# BlackIceMx.net
KiCad netlist of a schematic drawn in EAGLE
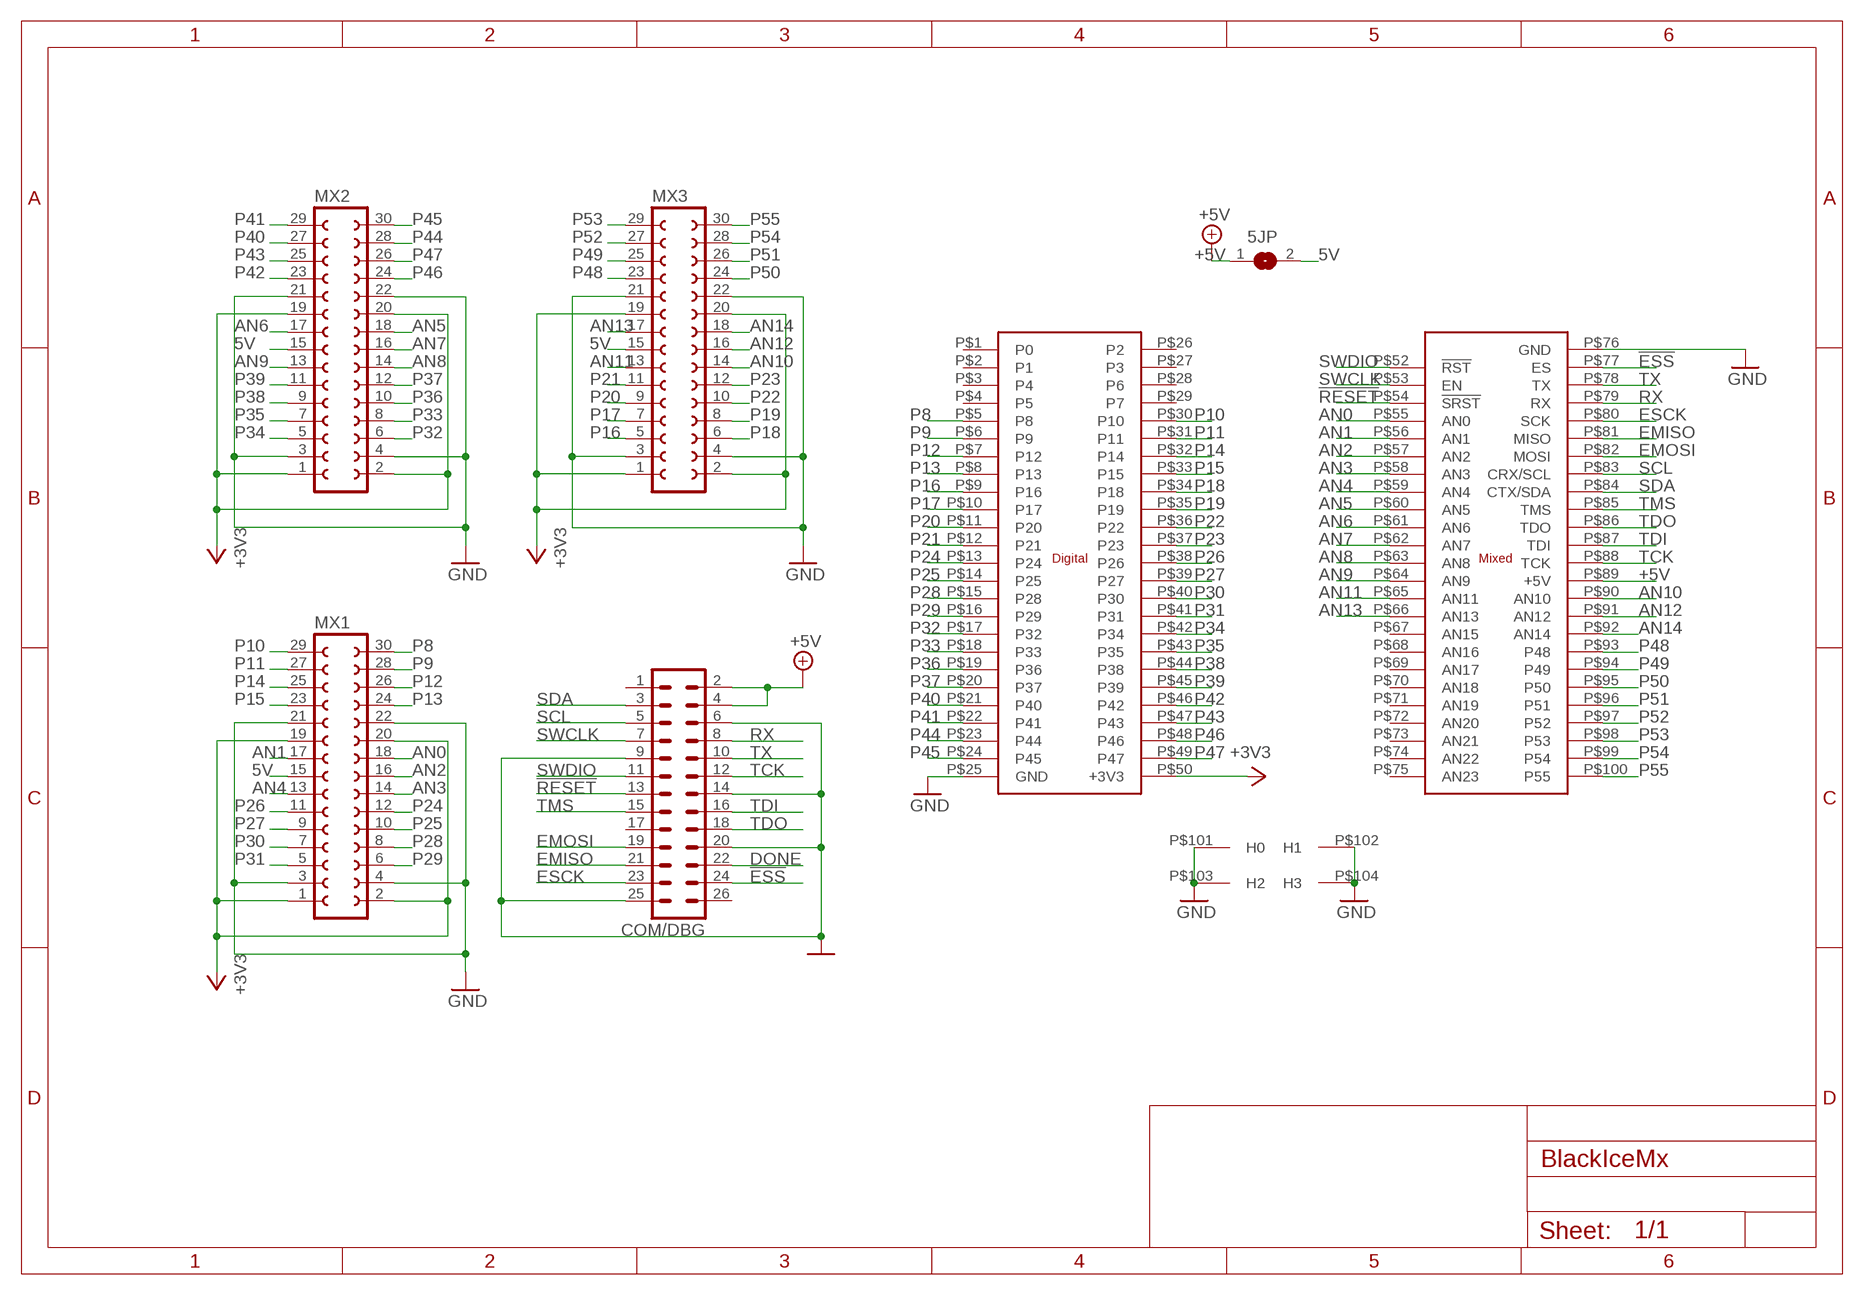
[diagram p0: schematic, sheet 1]

(export (version "E")
  (design (tool "Eeschema 10.0.6"))
  (components
    (comp (ref "5JP") (value "SJ") (footprint "eagle-import:SJ") (libsource (lib "eagle-import") (part "SJ")))
    (comp (ref "COM/DBG")
      (value "MA13-2")
      (footprint "eagle-import:MA13-2")
      (libsource (lib "eagle-import") (part "MA13-2"))
    )
    (comp (ref "MX1")
      (value "FE15-2")
      (footprint "eagle-import:FE15-2")
      (libsource (lib "eagle-import") (part "FE15-2"))
    )
    (comp (ref "MX2")
      (value "FE15-2")
      (footprint "eagle-import:FE15-2")
      (libsource (lib "eagle-import") (part "FE15-2"))
    )
    (comp (ref "MX3")
      (value "FE15-2")
      (footprint "eagle-import:FE15-2")
      (libsource (lib "eagle-import") (part "FE15-2"))
    )
    (comp (ref "U$1")
      (value "BE-CARRIERSMD")
      (footprint "eagle-import:BE-CARRIER-SMD")
      (libsource (lib "eagle-import") (part "BE-CARRIERSMD"))
    )
  )
  (nets
    (net (code "1") (name "+3V3") (class "Default")
      (node (ref "MX1") (pin "1") (pinfunction "1_1") (pintype "passive"))
      (node (ref "MX1") (pin "19") (pinfunction "19_19") (pintype "passive"))
      (node (ref "MX1") (pin "2") (pinfunction "2_2") (pintype "passive"))
      (node (ref "MX1") (pin "20") (pinfunction "20_20") (pintype "passive"))
      (node (ref "MX2") (pin "1") (pinfunction "1_1") (pintype "passive"))
      (node (ref "MX2") (pin "19") (pinfunction "19_19") (pintype "passive"))
      (node (ref "MX2") (pin "2") (pinfunction "2_2") (pintype "passive"))
      (node (ref "MX2") (pin "20") (pinfunction "20_20") (pintype "passive"))
      (node (ref "MX3") (pin "1") (pinfunction "1_1") (pintype "passive"))
      (node (ref "MX3") (pin "19") (pinfunction "19_19") (pintype "passive"))
      (node (ref "MX3") (pin "2") (pinfunction "2_2") (pintype "passive"))
      (node (ref "MX3") (pin "20") (pinfunction "20_20") (pintype "passive"))
      (node (ref "U$1") (pin "P$50") (pinfunction "+3V3_P$50") (pintype "power_in"))
    )
    (net (code "2") (name "+5V") (class "Default")
      (node (ref "5JP") (pin "1") (pinfunction "1_1") (pintype "passive"))
      (node (ref "COM/DBG") (pin "2") (pinfunction "2_2") (pintype "passive"))
      (node (ref "COM/DBG") (pin "4") (pinfunction "4_4") (pintype "passive"))
      (node (ref "U$1") (pin "P$89") (pinfunction "+5V_P$89") (pintype "power_in"))
    )
    (net (code "3") (name "/5V") (class "Default")
      (node (ref "5JP") (pin "2") (pinfunction "2_2") (pintype "passive"))
      (node (ref "MX1") (pin "15") (pinfunction "15_15") (pintype "passive"))
      (node (ref "MX2") (pin "15") (pinfunction "15_15") (pintype "passive"))
      (node (ref "MX3") (pin "15") (pinfunction "15_15") (pintype "passive"))
    )
    (net (code "4") (name "/AN0") (class "Default")
      (node (ref "MX1") (pin "18") (pinfunction "18_18") (pintype "passive"))
      (node (ref "U$1") (pin "P$55") (pinfunction "AN0_P$55") (pintype "bidirectional"))
    )
    (net (code "5") (name "/AN1") (class "Default")
      (node (ref "MX1") (pin "17") (pinfunction "17_17") (pintype "passive"))
      (node (ref "U$1") (pin "P$56") (pinfunction "AN1_P$56") (pintype "bidirectional"))
    )
    (net (code "6") (name "/AN2") (class "Default")
      (node (ref "MX1") (pin "16") (pinfunction "16_16") (pintype "passive"))
      (node (ref "U$1") (pin "P$57") (pinfunction "AN2_P$57") (pintype "bidirectional"))
    )
    (net (code "7") (name "/AN3") (class "Default")
      (node (ref "MX1") (pin "14") (pinfunction "14_14") (pintype "passive"))
      (node (ref "U$1") (pin "P$58") (pinfunction "AN3_P$58") (pintype "bidirectional"))
    )
    (net (code "8") (name "/AN4") (class "Default")
      (node (ref "MX1") (pin "13") (pinfunction "13_13") (pintype "passive"))
      (node (ref "U$1") (pin "P$59") (pinfunction "AN4_P$59") (pintype "bidirectional"))
    )
    (net (code "9") (name "/AN5") (class "Default")
      (node (ref "MX2") (pin "18") (pinfunction "18_18") (pintype "passive"))
      (node (ref "U$1") (pin "P$60") (pinfunction "AN5_P$60") (pintype "bidirectional"))
    )
    (net (code "10") (name "/AN6") (class "Default")
      (node (ref "MX2") (pin "17") (pinfunction "17_17") (pintype "passive"))
      (node (ref "U$1") (pin "P$61") (pinfunction "AN6_P$61") (pintype "bidirectional"))
    )
    (net (code "11") (name "/AN7") (class "Default")
      (node (ref "MX2") (pin "16") (pinfunction "16_16") (pintype "passive"))
      (node (ref "U$1") (pin "P$62") (pinfunction "AN7_P$62") (pintype "bidirectional"))
    )
    (net (code "12") (name "/AN8") (class "Default")
      (node (ref "MX2") (pin "14") (pinfunction "14_14") (pintype "passive"))
      (node (ref "U$1") (pin "P$63") (pinfunction "AN8_P$63") (pintype "bidirectional"))
    )
    (net (code "13") (name "/AN9") (class "Default")
      (node (ref "MX2") (pin "13") (pinfunction "13_13") (pintype "passive"))
      (node (ref "U$1") (pin "P$64") (pinfunction "AN9_P$64") (pintype "bidirectional"))
    )
    (net (code "14") (name "/AN10") (class "Default")
      (node (ref "MX3") (pin "14") (pinfunction "14_14") (pintype "passive"))
      (node (ref "U$1") (pin "P$90") (pinfunction "AN10_P$90") (pintype "bidirectional"))
    )
    (net (code "15") (name "/AN11") (class "Default")
      (node (ref "MX3") (pin "13") (pinfunction "13_13") (pintype "passive"))
      (node (ref "U$1") (pin "P$65") (pinfunction "AN11_P$65") (pintype "bidirectional"))
    )
    (net (code "16") (name "/AN12") (class "Default")
      (node (ref "MX3") (pin "16") (pinfunction "16_16") (pintype "passive"))
      (node (ref "U$1") (pin "P$91") (pinfunction "AN12_P$91") (pintype "bidirectional"))
    )
    (net (code "17") (name "/AN13") (class "Default")
      (node (ref "MX3") (pin "17") (pinfunction "17_17") (pintype "passive"))
      (node (ref "U$1") (pin "P$66") (pinfunction "AN13_P$66") (pintype "bidirectional"))
    )
    (net (code "18") (name "/AN14") (class "Default")
      (node (ref "MX3") (pin "18") (pinfunction "18_18") (pintype "passive"))
      (node (ref "U$1") (pin "P$92") (pinfunction "AN14_P$92") (pintype "bidirectional"))
    )
    (net (code "19") (name "/DONE") (class "Default")
      (node (ref "COM/DBG") (pin "22") (pinfunction "22_22") (pintype "passive"))
    )
    (net (code "20") (name "/EMISO") (class "Default")
      (node (ref "COM/DBG") (pin "21") (pinfunction "21_21") (pintype "passive"))
      (node (ref "U$1") (pin "P$81") (pinfunction "MISO_P$81") (pintype "bidirectional"))
    )
    (net (code "21") (name "/EMOSI") (class "Default")
      (node (ref "COM/DBG") (pin "19") (pinfunction "19_19") (pintype "passive"))
      (node (ref "U$1") (pin "P$82") (pinfunction "MOSI_P$82") (pintype "bidirectional"))
    )
    (net (code "22") (name "/ESCK") (class "Default")
      (node (ref "COM/DBG") (pin "23") (pinfunction "23_23") (pintype "passive"))
      (node (ref "U$1") (pin "P$80") (pinfunction "SCK_P$80") (pintype "bidirectional"))
    )
    (net (code "23") (name "/P8") (class "Default")
      (node (ref "MX1") (pin "30") (pinfunction "30_30") (pintype "passive"))
      (node (ref "U$1") (pin "P$5") (pinfunction "P8_P$5") (pintype "bidirectional"))
    )
    (net (code "24") (name "/P9") (class "Default")
      (node (ref "MX1") (pin "28") (pinfunction "28_28") (pintype "passive"))
      (node (ref "U$1") (pin "P$6") (pinfunction "P9_P$6") (pintype "bidirectional"))
    )
    (net (code "25") (name "/P10") (class "Default")
      (node (ref "MX1") (pin "29") (pinfunction "29_29") (pintype "passive"))
      (node (ref "U$1") (pin "P$30") (pinfunction "P10_P$30") (pintype "bidirectional"))
    )
    (net (code "26") (name "/P11") (class "Default")
      (node (ref "MX1") (pin "27") (pinfunction "27_27") (pintype "passive"))
      (node (ref "U$1") (pin "P$31") (pinfunction "P11_P$31") (pintype "bidirectional"))
    )
    (net (code "27") (name "/P12") (class "Default")
      (node (ref "MX1") (pin "26") (pinfunction "26_26") (pintype "passive"))
      (node (ref "U$1") (pin "P$7") (pinfunction "P12_P$7") (pintype "bidirectional"))
    )
    (net (code "28") (name "/P13") (class "Default")
      (node (ref "MX1") (pin "24") (pinfunction "24_24") (pintype "passive"))
      (node (ref "U$1") (pin "P$8") (pinfunction "P13_P$8") (pintype "bidirectional"))
    )
    (net (code "29") (name "/P14") (class "Default")
      (node (ref "MX1") (pin "25") (pinfunction "25_25") (pintype "passive"))
      (node (ref "U$1") (pin "P$32") (pinfunction "P14_P$32") (pintype "bidirectional"))
    )
    (net (code "30") (name "/P15") (class "Default")
      (node (ref "MX1") (pin "23") (pinfunction "23_23") (pintype "passive"))
      (node (ref "U$1") (pin "P$33") (pinfunction "P15_P$33") (pintype "bidirectional"))
    )
    (net (code "31") (name "/P16") (class "Default")
      (node (ref "MX3") (pin "5") (pinfunction "5_5") (pintype "passive"))
      (node (ref "U$1") (pin "P$9") (pinfunction "P16_P$9") (pintype "bidirectional"))
    )
    (net (code "32") (name "/P17") (class "Default")
      (node (ref "MX3") (pin "7") (pinfunction "7_7") (pintype "passive"))
      (node (ref "U$1") (pin "P$10") (pinfunction "P17_P$10") (pintype "bidirectional"))
    )
    (net (code "33") (name "/P18") (class "Default")
      (node (ref "MX3") (pin "6") (pinfunction "6_6") (pintype "passive"))
      (node (ref "U$1") (pin "P$34") (pinfunction "P18_P$34") (pintype "bidirectional"))
    )
    (net (code "34") (name "/P19") (class "Default")
      (node (ref "MX3") (pin "8") (pinfunction "8_8") (pintype "passive"))
      (node (ref "U$1") (pin "P$35") (pinfunction "P19_P$35") (pintype "bidirectional"))
    )
    (net (code "35") (name "/P20") (class "Default")
      (node (ref "MX3") (pin "9") (pinfunction "9_9") (pintype "passive"))
      (node (ref "U$1") (pin "P$11") (pinfunction "P20_P$11") (pintype "bidirectional"))
    )
    (net (code "36") (name "/P21") (class "Default")
      (node (ref "MX3") (pin "11") (pinfunction "11_11") (pintype "passive"))
      (node (ref "U$1") (pin "P$12") (pinfunction "P21_P$12") (pintype "bidirectional"))
    )
    (net (code "37") (name "/P22") (class "Default")
      (node (ref "MX3") (pin "10") (pinfunction "10_10") (pintype "passive"))
      (node (ref "U$1") (pin "P$36") (pinfunction "P22_P$36") (pintype "bidirectional"))
    )
    (net (code "38") (name "/P23") (class "Default")
      (node (ref "MX3") (pin "12") (pinfunction "12_12") (pintype "passive"))
      (node (ref "U$1") (pin "P$37") (pinfunction "P23_P$37") (pintype "bidirectional"))
    )
    (net (code "39") (name "/P24") (class "Default")
      (node (ref "MX1") (pin "12") (pinfunction "12_12") (pintype "passive"))
      (node (ref "U$1") (pin "P$13") (pinfunction "P24_P$13") (pintype "bidirectional"))
    )
    (net (code "40") (name "/P25") (class "Default")
      (node (ref "MX1") (pin "10") (pinfunction "10_10") (pintype "passive"))
      (node (ref "U$1") (pin "P$14") (pinfunction "P25_P$14") (pintype "bidirectional"))
    )
    (net (code "41") (name "/P26") (class "Default")
      (node (ref "MX1") (pin "11") (pinfunction "11_11") (pintype "passive"))
      (node (ref "U$1") (pin "P$38") (pinfunction "P26_P$38") (pintype "bidirectional"))
    )
    (net (code "42") (name "/P27") (class "Default")
      (node (ref "MX1") (pin "9") (pinfunction "9_9") (pintype "passive"))
      (node (ref "U$1") (pin "P$39") (pinfunction "P27_P$39") (pintype "bidirectional"))
    )
    (net (code "43") (name "/P28") (class "Default")
      (node (ref "MX1") (pin "8") (pinfunction "8_8") (pintype "passive"))
      (node (ref "U$1") (pin "P$15") (pinfunction "P28_P$15") (pintype "bidirectional"))
    )
    (net (code "44") (name "/P29") (class "Default")
      (node (ref "MX1") (pin "6") (pinfunction "6_6") (pintype "passive"))
      (node (ref "U$1") (pin "P$16") (pinfunction "P29_P$16") (pintype "bidirectional"))
    )
    (net (code "45") (name "/P30") (class "Default")
      (node (ref "MX1") (pin "7") (pinfunction "7_7") (pintype "passive"))
      (node (ref "U$1") (pin "P$40") (pinfunction "P30_P$40") (pintype "bidirectional"))
    )
    (net (code "46") (name "/P31") (class "Default")
      (node (ref "MX1") (pin "5") (pinfunction "5_5") (pintype "passive"))
      (node (ref "U$1") (pin "P$41") (pinfunction "P31_P$41") (pintype "bidirectional"))
    )
    (net (code "47") (name "/P32") (class "Default")
      (node (ref "MX2") (pin "6") (pinfunction "6_6") (pintype "passive"))
      (node (ref "U$1") (pin "P$17") (pinfunction "P32_P$17") (pintype "bidirectional"))
    )
    (net (code "48") (name "/P33") (class "Default")
      (node (ref "MX2") (pin "8") (pinfunction "8_8") (pintype "passive"))
      (node (ref "U$1") (pin "P$18") (pinfunction "P33_P$18") (pintype "bidirectional"))
    )
    (net (code "49") (name "/P34") (class "Default")
      (node (ref "MX2") (pin "5") (pinfunction "5_5") (pintype "passive"))
      (node (ref "U$1") (pin "P$42") (pinfunction "P34_P$42") (pintype "bidirectional"))
    )
    (net (code "50") (name "/P35") (class "Default")
      (node (ref "MX2") (pin "7") (pinfunction "7_7") (pintype "passive"))
      (node (ref "U$1") (pin "P$43") (pinfunction "P35_P$43") (pintype "bidirectional"))
    )
    (net (code "51") (name "/P36") (class "Default")
      (node (ref "MX2") (pin "10") (pinfunction "10_10") (pintype "passive"))
      (node (ref "U$1") (pin "P$19") (pinfunction "P36_P$19") (pintype "bidirectional"))
    )
    (net (code "52") (name "/P37") (class "Default")
      (node (ref "MX2") (pin "12") (pinfunction "12_12") (pintype "passive"))
      (node (ref "U$1") (pin "P$20") (pinfunction "P37_P$20") (pintype "bidirectional"))
    )
    (net (code "53") (name "/P38") (class "Default")
      (node (ref "MX2") (pin "9") (pinfunction "9_9") (pintype "passive"))
      (node (ref "U$1") (pin "P$44") (pinfunction "P38_P$44") (pintype "bidirectional"))
    )
    (net (code "54") (name "/P39") (class "Default")
      (node (ref "MX2") (pin "11") (pinfunction "11_11") (pintype "passive"))
      (node (ref "U$1") (pin "P$45") (pinfunction "P39_P$45") (pintype "bidirectional"))
    )
    (net (code "55") (name "/P40") (class "Default")
      (node (ref "MX2") (pin "27") (pinfunction "27_27") (pintype "passive"))
      (node (ref "U$1") (pin "P$21") (pinfunction "P40_P$21") (pintype "bidirectional"))
    )
    (net (code "56") (name "/P41") (class "Default")
      (node (ref "MX2") (pin "29") (pinfunction "29_29") (pintype "passive"))
      (node (ref "U$1") (pin "P$22") (pinfunction "P41_P$22") (pintype "bidirectional"))
    )
    (net (code "57") (name "/P42") (class "Default")
      (node (ref "MX2") (pin "23") (pinfunction "23_23") (pintype "passive"))
      (node (ref "U$1") (pin "P$46") (pinfunction "P42_P$46") (pintype "bidirectional"))
    )
    (net (code "58") (name "/P43") (class "Default")
      (node (ref "MX2") (pin "25") (pinfunction "25_25") (pintype "passive"))
      (node (ref "U$1") (pin "P$47") (pinfunction "P43_P$47") (pintype "bidirectional"))
    )
    (net (code "59") (name "/P44") (class "Default")
      (node (ref "MX2") (pin "28") (pinfunction "28_28") (pintype "passive"))
      (node (ref "U$1") (pin "P$23") (pinfunction "P44_P$23") (pintype "bidirectional"))
    )
    (net (code "60") (name "/P45") (class "Default")
      (node (ref "MX2") (pin "30") (pinfunction "30_30") (pintype "passive"))
      (node (ref "U$1") (pin "P$24") (pinfunction "P45_P$24") (pintype "bidirectional"))
    )
    (net (code "61") (name "/P46") (class "Default")
      (node (ref "MX2") (pin "24") (pinfunction "24_24") (pintype "passive"))
      (node (ref "U$1") (pin "P$48") (pinfunction "P46_P$48") (pintype "bidirectional"))
    )
    (net (code "62") (name "/P47") (class "Default")
      (node (ref "MX2") (pin "26") (pinfunction "26_26") (pintype "passive"))
      (node (ref "U$1") (pin "P$49") (pinfunction "P47_P$49") (pintype "bidirectional"))
    )
    (net (code "63") (name "/P48") (class "Default")
      (node (ref "MX3") (pin "23") (pinfunction "23_23") (pintype "passive"))
      (node (ref "U$1") (pin "P$93") (pinfunction "P48_P$93") (pintype "bidirectional"))
    )
    (net (code "64") (name "/P49") (class "Default")
      (node (ref "MX3") (pin "25") (pinfunction "25_25") (pintype "passive"))
      (node (ref "U$1") (pin "P$94") (pinfunction "P49_P$94") (pintype "bidirectional"))
    )
    (net (code "65") (name "/P50") (class "Default")
      (node (ref "MX3") (pin "24") (pinfunction "24_24") (pintype "passive"))
      (node (ref "U$1") (pin "P$95") (pinfunction "P50_P$95") (pintype "bidirectional"))
    )
    (net (code "66") (name "/P51") (class "Default")
      (node (ref "MX3") (pin "26") (pinfunction "26_26") (pintype "passive"))
      (node (ref "U$1") (pin "P$96") (pinfunction "P51_P$96") (pintype "bidirectional"))
    )
    (net (code "67") (name "/P52") (class "Default")
      (node (ref "MX3") (pin "27") (pinfunction "27_27") (pintype "passive"))
      (node (ref "U$1") (pin "P$97") (pinfunction "P52_P$97") (pintype "bidirectional"))
    )
    (net (code "68") (name "/P53") (class "Default")
      (node (ref "MX3") (pin "29") (pinfunction "29_29") (pintype "passive"))
      (node (ref "U$1") (pin "P$98") (pinfunction "P53_P$98") (pintype "bidirectional"))
    )
    (net (code "69") (name "/P54") (class "Default")
      (node (ref "MX3") (pin "28") (pinfunction "28_28") (pintype "passive"))
      (node (ref "U$1") (pin "P$99") (pinfunction "P54_P$99") (pintype "bidirectional"))
    )
    (net (code "70") (name "/P55") (class "Default")
      (node (ref "MX3") (pin "30") (pinfunction "30_30") (pintype "passive"))
      (node (ref "U$1") (pin "P$100") (pinfunction "P55_P$100") (pintype "bidirectional"))
    )
    (net (code "71") (name "/RX") (class "Default")
      (node (ref "COM/DBG") (pin "8") (pinfunction "8_8") (pintype "passive"))
      (node (ref "U$1") (pin "P$79") (pinfunction "RX_P$79") (pintype "bidirectional"))
    )
    (net (code "72") (name "/SCL") (class "Default")
      (node (ref "COM/DBG") (pin "5") (pinfunction "5_5") (pintype "passive"))
      (node (ref "U$1") (pin "P$83") (pinfunction "CRX/SCL_P$83") (pintype "bidirectional"))
    )
    (net (code "73") (name "/SDA") (class "Default")
      (node (ref "COM/DBG") (pin "3") (pinfunction "3_3") (pintype "passive"))
      (node (ref "U$1") (pin "P$84") (pinfunction "CTX/SDA_P$84") (pintype "bidirectional"))
    )
    (net (code "74") (name "/SWCLK") (class "Default")
      (node (ref "COM/DBG") (pin "7") (pinfunction "7_7") (pintype "passive"))
      (node (ref "U$1") (pin "P$53") (pinfunction "EN_P$53") (pintype "bidirectional"))
    )
    (net (code "75") (name "/SWDIO") (class "Default")
      (node (ref "COM/DBG") (pin "11") (pinfunction "11_11") (pintype "passive"))
      (node (ref "U$1") (pin "P$52") (pinfunction "~{RST}_P$52") (pintype "bidirectional"))
    )
    (net (code "76") (name "/TCK") (class "Default")
      (node (ref "COM/DBG") (pin "12") (pinfunction "12_12") (pintype "passive"))
      (node (ref "U$1") (pin "P$88") (pinfunction "TCK_P$88") (pintype "bidirectional"))
    )
    (net (code "77") (name "/TDI") (class "Default")
      (node (ref "COM/DBG") (pin "16") (pinfunction "16_16") (pintype "passive"))
      (node (ref "U$1") (pin "P$87") (pinfunction "TDI_P$87") (pintype "power_in"))
    )
    (net (code "78") (name "/TDO") (class "Default")
      (node (ref "COM/DBG") (pin "18") (pinfunction "18_18") (pintype "passive"))
      (node (ref "U$1") (pin "P$86") (pinfunction "TDO_P$86") (pintype "bidirectional"))
    )
    (net (code "79") (name "/TMS") (class "Default")
      (node (ref "COM/DBG") (pin "15") (pinfunction "15_15") (pintype "passive"))
      (node (ref "U$1") (pin "P$85") (pinfunction "TMS_P$85") (pintype "bidirectional"))
    )
    (net (code "80") (name "/TX") (class "Default")
      (node (ref "COM/DBG") (pin "10") (pinfunction "10_10") (pintype "passive"))
      (node (ref "U$1") (pin "P$78") (pinfunction "TX_P$78") (pintype "bidirectional"))
    )
    (net (code "81") (name "/~{ESS}") (class "Default")
      (node (ref "COM/DBG") (pin "24") (pinfunction "24_24") (pintype "passive"))
      (node (ref "U$1") (pin "P$77") (pinfunction "ES_P$77") (pintype "bidirectional"))
    )
    (net (code "82") (name "/~{RESET}") (class "Default")
      (node (ref "COM/DBG") (pin "13") (pinfunction "13_13") (pintype "passive"))
      (node (ref "U$1") (pin "P$54") (pinfunction "~{SRST}_P$54") (pintype "bidirectional"))
    )
    (net (code "83") (name "GND") (class "Default")
      (node (ref "COM/DBG") (pin "14") (pinfunction "14_14") (pintype "passive"))
      (node (ref "COM/DBG") (pin "20") (pinfunction "20_20") (pintype "passive"))
      (node (ref "COM/DBG") (pin "25") (pinfunction "25_25") (pintype "passive"))
      (node (ref "COM/DBG") (pin "6") (pinfunction "6_6") (pintype "passive"))
      (node (ref "COM/DBG") (pin "9") (pinfunction "9_9") (pintype "passive"))
      (node (ref "MX1") (pin "21") (pinfunction "21_21") (pintype "passive"))
      (node (ref "MX1") (pin "22") (pinfunction "22_22") (pintype "passive"))
      (node (ref "MX1") (pin "3") (pinfunction "3_3") (pintype "passive"))
      (node (ref "MX1") (pin "4") (pinfunction "4_4") (pintype "passive"))
      (node (ref "MX2") (pin "21") (pinfunction "21_21") (pintype "passive"))
      (node (ref "MX2") (pin "22") (pinfunction "22_22") (pintype "passive"))
      (node (ref "MX2") (pin "3") (pinfunction "3_3") (pintype "passive"))
      (node (ref "MX2") (pin "4") (pinfunction "4_4") (pintype "passive"))
      (node (ref "MX3") (pin "21") (pinfunction "21_21") (pintype "passive"))
      (node (ref "MX3") (pin "22") (pinfunction "22_22") (pintype "passive"))
      (node (ref "MX3") (pin "3") (pinfunction "3_3") (pintype "passive"))
      (node (ref "MX3") (pin "4") (pinfunction "4_4") (pintype "passive"))
      (node (ref "U$1") (pin "P$101") (pinfunction "H0_P$101") (pintype "bidirectional"))
      (node (ref "U$1") (pin "P$102") (pinfunction "H1_P$102") (pintype "bidirectional"))
      (node (ref "U$1") (pin "P$103") (pinfunction "H2_P$103") (pintype "bidirectional"))
      (node (ref "U$1") (pin "P$104") (pinfunction "H3_P$104") (pintype "bidirectional"))
      (node (ref "U$1") (pin "P$25") (pinfunction "GND_P$25") (pintype "power_in"))
      (node (ref "U$1") (pin "P$76") (pinfunction "GND_P$76") (pintype "power_in"))
    )
    (net (code "84") (name "unconnected-(COM/DBG-Pad1)") (class "Default")
      (node (ref "COM/DBG") (pin "1") (pinfunction "1_1") (pintype "passive"))
    )
    (net (code "85") (name "unconnected-(COM/DBG-Pad17)") (class "Default")
      (node (ref "COM/DBG") (pin "17") (pinfunction "17_17") (pintype "passive"))
    )
    (net (code "86") (name "unconnected-(COM/DBG-Pad26)") (class "Default")
      (node (ref "COM/DBG") (pin "26") (pinfunction "26_26") (pintype "passive"))
    )
    (net (code "87") (name "unconnected-(U$1-AN15-PadP$67)") (class "Default")
      (node (ref "U$1") (pin "P$67") (pinfunction "AN15_P$67") (pintype "bidirectional"))
    )
    (net (code "88") (name "unconnected-(U$1-AN16-PadP$68)") (class "Default")
      (node (ref "U$1") (pin "P$68") (pinfunction "AN16_P$68") (pintype "bidirectional"))
    )
    (net (code "89") (name "unconnected-(U$1-AN17-PadP$69)") (class "Default")
      (node (ref "U$1") (pin "P$69") (pinfunction "AN17_P$69") (pintype "bidirectional"))
    )
    (net (code "90") (name "unconnected-(U$1-AN18-PadP$70)") (class "Default")
      (node (ref "U$1") (pin "P$70") (pinfunction "AN18_P$70") (pintype "bidirectional"))
    )
    (net (code "91") (name "unconnected-(U$1-AN19-PadP$71)") (class "Default")
      (node (ref "U$1") (pin "P$71") (pinfunction "AN19_P$71") (pintype "bidirectional"))
    )
    (net (code "92") (name "unconnected-(U$1-AN20-PadP$72)") (class "Default")
      (node (ref "U$1") (pin "P$72") (pinfunction "AN20_P$72") (pintype "bidirectional"))
    )
    (net (code "93") (name "unconnected-(U$1-AN21-PadP$73)") (class "Default")
      (node (ref "U$1") (pin "P$73") (pinfunction "AN21_P$73") (pintype "bidirectional"))
    )
    (net (code "94") (name "unconnected-(U$1-AN22-PadP$74)") (class "Default")
      (node (ref "U$1") (pin "P$74") (pinfunction "AN22_P$74") (pintype "bidirectional"))
    )
    (net (code "95") (name "unconnected-(U$1-AN23-PadP$75)") (class "Default")
      (node (ref "U$1") (pin "P$75") (pinfunction "AN23_P$75") (pintype "bidirectional"))
    )
    (net (code "96") (name "unconnected-(U$1-NC-PadP$51)") (class "Default")
      (node (ref "U$1") (pin "P$51") (pinfunction "NC_P$51") (pintype "no_connect"))
    )
    (net (code "97") (name "unconnected-(U$1-P0-PadP$1)") (class "Default")
      (node (ref "U$1") (pin "P$1") (pinfunction "P0_P$1") (pintype "bidirectional"))
    )
    (net (code "98") (name "unconnected-(U$1-P1-PadP$2)") (class "Default")
      (node (ref "U$1") (pin "P$2") (pinfunction "P1_P$2") (pintype "bidirectional"))
    )
    (net (code "99") (name "unconnected-(U$1-P2-PadP$26)") (class "Default")
      (node (ref "U$1") (pin "P$26") (pinfunction "P2_P$26") (pintype "bidirectional"))
    )
    (net (code "100") (name "unconnected-(U$1-P3-PadP$27)") (class "Default")
      (node (ref "U$1") (pin "P$27") (pinfunction "P3_P$27") (pintype "bidirectional"))
    )
    (net (code "101") (name "unconnected-(U$1-P4-PadP$3)") (class "Default")
      (node (ref "U$1") (pin "P$3") (pinfunction "P4_P$3") (pintype "bidirectional"))
    )
    (net (code "102") (name "unconnected-(U$1-P5-PadP$4)") (class "Default")
      (node (ref "U$1") (pin "P$4") (pinfunction "P5_P$4") (pintype "bidirectional"))
    )
    (net (code "103") (name "unconnected-(U$1-P6-PadP$28)") (class "Default")
      (node (ref "U$1") (pin "P$28") (pinfunction "P6_P$28") (pintype "bidirectional"))
    )
    (net (code "104") (name "unconnected-(U$1-P7-PadP$29)") (class "Default")
      (node (ref "U$1") (pin "P$29") (pinfunction "P7_P$29") (pintype "bidirectional"))
    )
  )
)
